# IMU.net
KiCad netlist of a schematic drawn in Altium Designer
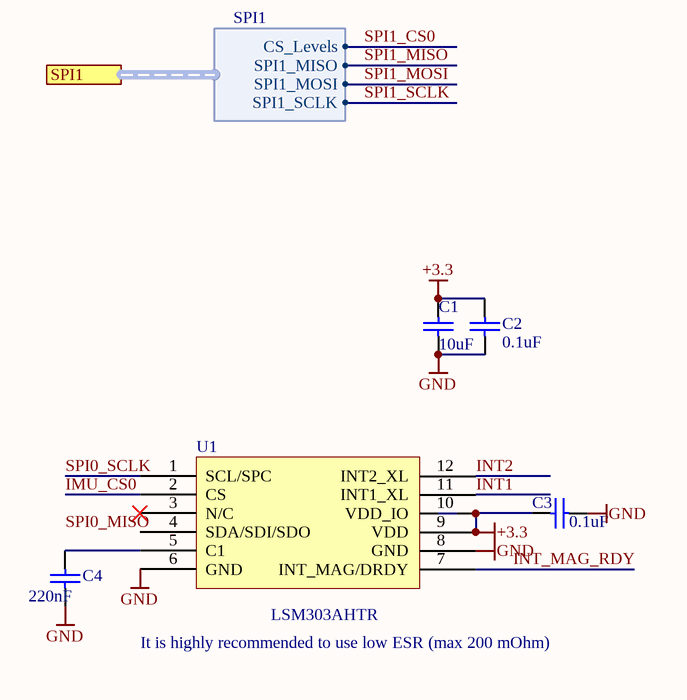
[diagram p0: IMU.SchDoc]

(export (version "E")
  (design (tool "Eeschema 10.0.6"))
  (components
    (comp (ref "C1")
      (value "10uF")
      (footprint "CAPC0402(1005)60_L")
      (description "CAP CER 0.1UF 10V X7R 0402")
      (fields
        (field (name "MANUFACTURER") "Murata Electronics North America")
        (field (name "MANUFACTURER PART NUMBER") "GRM155R71A104KA01D")
      )
      (libsource (lib "Altium Content Vault") (part "CMP-1034-00252-1"))
    )
    (comp (ref "C2")
      (value "0.1uF")
      (footprint "CAPC0402(1005)60_L")
      (description "CAP CER 0.1UF 10V X7R 0402")
      (fields
        (field (name "MANUFACTURER") "Murata Electronics North America")
        (field (name "MANUFACTURER PART NUMBER") "GRM155R71A104KA01D")
      )
      (libsource (lib "Altium Content Vault") (part "CMP-1034-00252-1"))
    )
    (comp (ref "C3")
      (value "0.1uF")
      (footprint "CAPC0402(1005)60_L")
      (description "CAP CER 0.1UF 10V X7R 0402")
      (fields
        (field (name "MANUFACTURER") "Murata Electronics North America")
        (field (name "MANUFACTURER PART NUMBER") "GRM155R71A104KA01D")
      )
      (libsource (lib "Altium Content Vault") (part "CMP-1034-00252-1"))
    )
    (comp (ref "C4")
      (value "220nF")
      (footprint "CAPC0402(1005)60_L")
      (description "CAP CER 0.1UF 10V X7R 0402")
      (fields
        (field (name "MANUFACTURER") "Murata Electronics North America")
        (field (name "MANUFACTURER PART NUMBER") "GRM155R71A104KA01D")
      )
      (libsource (lib "Altium Content Vault") (part "CMP-1034-00252-1"))
    )
    (comp (ref "U1")
      (value "LSM303AHTR")
      (footprint "LSM303AHTR")
      (description "ULTRA-COMPACT HIGH-PERFORMANCE E")
      (fields (field (name "MANUFACTURER") "STMicroelectronics"))
      (libsource (lib "ZLS_Schematic_lib") (part "LSM303AHTR"))
    )
  )
  (nets
    (net (code "2") (name "+3.3") (class "Default")
      (node (ref "C1") (pin "2") (pinfunction "2_2") (pintype "passive"))
      (node (ref "C2") (pin "1") (pinfunction "1_1") (pintype "passive"))
      (node (ref "C3") (pin "1") (pinfunction "1_1") (pintype "passive"))
      (node (ref "U1") (pin "10") (pinfunction "VDD_IO_10") (pintype "passive"))
      (node (ref "U1") (pin "9") (pinfunction "VDD_9") (pintype "passive"))
    )
    (net (code "3") (name "/IMU_CS0") (class "Default")
      (node (ref "U1") (pin "2") (pinfunction "CS_2") (pintype "passive"))
    )
    (net (code "4") (name "/INT1") (class "Default")
      (node (ref "U1") (pin "11") (pinfunction "INT1_XL_11") (pintype "passive"))
    )
    (net (code "5") (name "/INT2") (class "Default")
      (node (ref "U1") (pin "12") (pinfunction "INT2_XL_12") (pintype "passive"))
    )
    (net (code "6") (name "/INT_MAG_RDY") (class "Default")
      (node (ref "U1") (pin "7") (pinfunction "INT_MAG/DRDY_7") (pintype "passive"))
    )
    (net (code "8") (name "/SPI0_SCLK") (class "Default")
      (node (ref "U1") (pin "1") (pinfunction "SCL/SPC_1") (pintype "passive"))
    )
    (net (code "14") (name "GND") (class "Default")
      (node (ref "C1") (pin "1") (pinfunction "1_1") (pintype "passive"))
      (node (ref "C2") (pin "2") (pinfunction "2_2") (pintype "passive"))
      (node (ref "C3") (pin "2") (pinfunction "2_2") (pintype "passive"))
      (node (ref "C4") (pin "1") (pinfunction "1_1") (pintype "passive"))
      (node (ref "U1") (pin "6") (pinfunction "GND_6") (pintype "passive"))
      (node (ref "U1") (pin "8") (pinfunction "GND_8") (pintype "passive"))
    )
    (net (code "15") (name "Net-(U1-C1)") (class "Default")
      (node (ref "C4") (pin "2") (pinfunction "2_2") (pintype "passive"))
      (node (ref "U1") (pin "5") (pinfunction "C1_5") (pintype "passive"))
    )
    (net (code "16") (name "unconnected-(U1-N{slash}C-Pad3)") (class "Default")
      (node (ref "U1") (pin "3") (pinfunction "N/C_3") (pintype "passive+no_connect"))
    )
    (net (code "17") (name "unconnected-(U1-SDA{slash}SDI{slash}SDO-Pad4)") (class "Default")
      (node (ref "U1") (pin "4") (pinfunction "SDA/SDI/SDO_4") (pintype "passive"))
    )
  )
)
